# 1.net
KiCad netlist of a schematic drawn in EAGLE
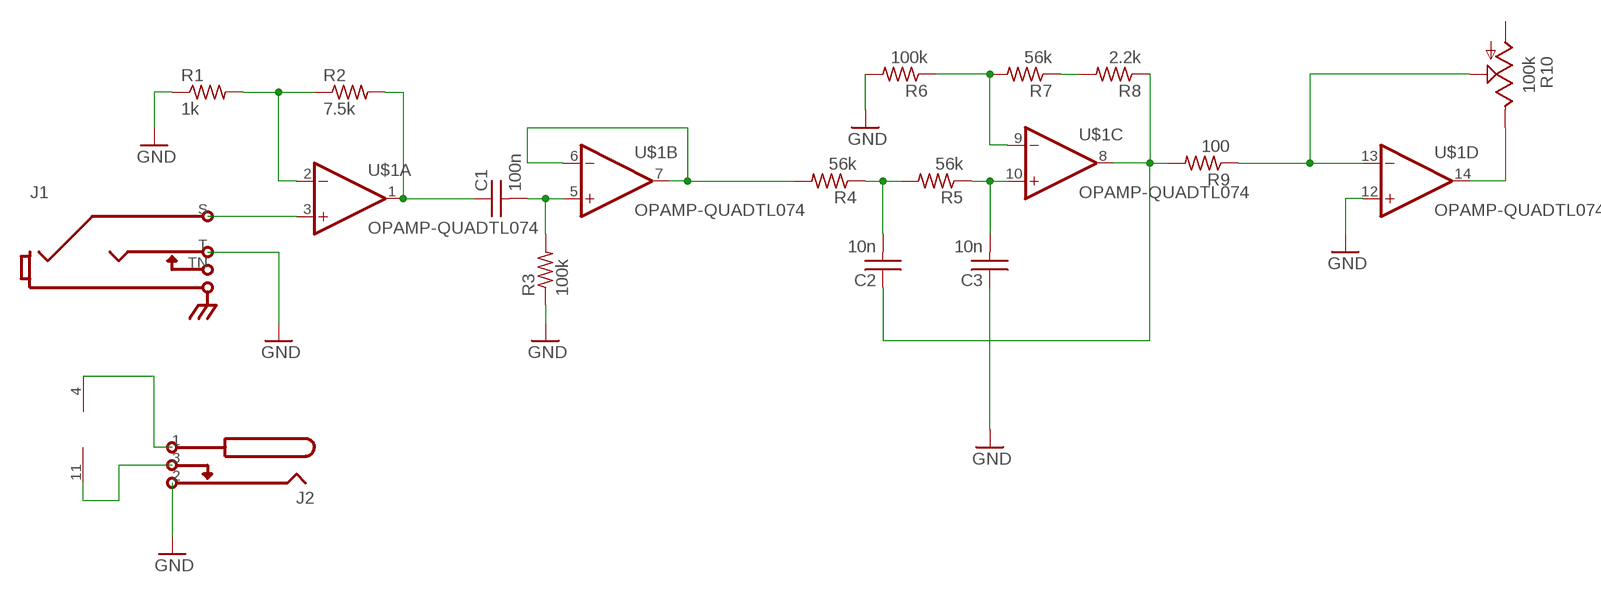
[diagram p0: schematic, sheet 1]

(export (version "E")
  (design (tool "Eeschema 10.0.6"))
  (components
    (comp (ref "C1")
      (value "100n")
      (footprint "eagle-import:BOX-2.5MM-7.2MM")
      (libsource (lib "eagle-import") (part "CAPACITOR"))
    )
    (comp (ref "C2")
      (value "10n")
      (footprint "eagle-import:BOX-2.5MM-7.2MM")
      (libsource (lib "eagle-import") (part "CAPACITOR"))
    )
    (comp (ref "C3")
      (value "10n")
      (footprint "eagle-import:BOX-2.5MM-7.2MM")
      (libsource (lib "eagle-import") (part "CAPACITOR"))
    )
    (comp (ref "J1")
      (value "MONOSW1GND")
      (footprint "eagle-import:NEUTRIK-NRJ4HM-1")
      (libsource (lib "eagle-import") (part "MONOSW1GND"))
    )
    (comp (ref "J2")
      (value "BOSS-SWITCHING")
      (footprint "eagle-import:KOBICONN-163-5010-E")
      (libsource (lib "eagle-import") (part "BOSS-SWITCHING"))
    )
    (comp (ref "R1")
      (value "1k")
      (footprint "eagle-import:0.25W-0.4IN-CARBONCOMP")
      (libsource (lib "eagle-import") (part "RESISTOR0.25W-0.4IN-CARBONCOMP"))
    )
    (comp (ref "R2")
      (value "7.5k")
      (footprint "eagle-import:0.25W-0.4IN-CARBONCOMP")
      (libsource (lib "eagle-import") (part "RESISTOR0.25W-0.4IN-CARBONCOMP"))
    )
    (comp (ref "R3")
      (value "100k")
      (footprint "eagle-import:0.25W-0.4IN-CARBONCOMP")
      (libsource (lib "eagle-import") (part "RESISTOR0.25W-0.4IN-CARBONCOMP"))
    )
    (comp (ref "R4")
      (value "56k")
      (footprint "eagle-import:0.25W-0.4IN-CARBONCOMP")
      (libsource (lib "eagle-import") (part "RESISTOR0.25W-0.4IN-CARBONCOMP"))
    )
    (comp (ref "R5")
      (value "56k")
      (footprint "eagle-import:0.25W-0.4IN-CARBONCOMP")
      (libsource (lib "eagle-import") (part "RESISTOR0.25W-0.4IN-CARBONCOMP"))
    )
    (comp (ref "R6")
      (value "100k")
      (footprint "eagle-import:0.25W-0.4IN-CARBONCOMP")
      (libsource (lib "eagle-import") (part "RESISTOR0.25W-0.4IN-CARBONCOMP"))
    )
    (comp (ref "R7")
      (value "56k")
      (footprint "eagle-import:0.25W-0.4IN-CARBONCOMP")
      (libsource (lib "eagle-import") (part "RESISTOR0.25W-0.4IN-CARBONCOMP"))
    )
    (comp (ref "R8")
      (value "2.2k")
      (footprint "eagle-import:0.25W-0.4IN-CARBONCOMP")
      (libsource (lib "eagle-import") (part "RESISTOR0.25W-0.4IN-CARBONCOMP"))
    )
    (comp (ref "R9")
      (value "100")
      (footprint "eagle-import:0.25W-0.4IN-CARBONCOMP")
      (libsource (lib "eagle-import") (part "RESISTOR0.25W-0.4IN-CARBONCOMP"))
    )
    (comp (ref "R10")
      (value "100k")
      (footprint "eagle-import:POT-SIDE-16MM-BITECH-P160KN")
      (libsource (lib "eagle-import") (part "POTENTIOMETERHORIZONTAL"))
    )
    (comp (ref "U$1")
      (value "OPAMP-QUADTL074")
      (footprint "eagle-import:DIP14")
      (libsource (lib "eagle-import") (part "OPAMP-QUADTL074"))
    )
  )
  (nets
    (net (code "1") (name "0") (class "Default")
      (node (ref "C3") (pin "P$1") (pinfunction "1_P$1") (pintype "passive"))
      (node (ref "J1") (pin "T") (pinfunction "T_T") (pintype "passive"))
      (node (ref "J2") (pin "2") (pinfunction "VCC_2") (pintype "passive"))
      (node (ref "R1") (pin "1") (pinfunction "1_1") (pintype "passive"))
      (node (ref "R3") (pin "1") (pinfunction "1_1") (pintype "passive"))
      (node (ref "R6") (pin "2") (pinfunction "2_2") (pintype "passive"))
      (node (ref "U$1") (pin "12") (pinfunction "IN+_12") (pintype "input"))
    )
    (net (code "2") (name "Net-(C1-1)") (class "Default")
      (node (ref "C1") (pin "P$1") (pinfunction "1_P$1") (pintype "passive"))
      (node (ref "R2") (pin "2") (pinfunction "2_2") (pintype "passive"))
      (node (ref "U$1") (pin "1") (pinfunction "OUT_1") (pintype "output"))
    )
    (net (code "3") (name "Net-(C1-2)") (class "Default")
      (node (ref "C1") (pin "P$2") (pinfunction "2_P$2") (pintype "passive"))
      (node (ref "R3") (pin "2") (pinfunction "2_2") (pintype "passive"))
      (node (ref "U$1") (pin "5") (pinfunction "IN+_5") (pintype "input"))
    )
    (net (code "4") (name "Net-(C2-1)") (class "Default")
      (node (ref "C2") (pin "P$1") (pinfunction "1_P$1") (pintype "passive"))
      (node (ref "R8") (pin "1") (pinfunction "1_1") (pintype "passive"))
      (node (ref "R9") (pin "2") (pinfunction "2_2") (pintype "passive"))
      (node (ref "U$1") (pin "8") (pinfunction "OUT_8") (pintype "output"))
    )
    (net (code "5") (name "Net-(C2-2)") (class "Default")
      (node (ref "C2") (pin "P$2") (pinfunction "2_P$2") (pintype "passive"))
      (node (ref "R4") (pin "1") (pinfunction "1_1") (pintype "passive"))
      (node (ref "R5") (pin "2") (pinfunction "2_2") (pintype "passive"))
    )
    (net (code "6") (name "Net-(C3-2)") (class "Default")
      (node (ref "C3") (pin "P$2") (pinfunction "2_P$2") (pintype "passive"))
      (node (ref "R5") (pin "1") (pinfunction "1_1") (pintype "passive"))
      (node (ref "U$1") (pin "10") (pinfunction "IN+_10") (pintype "input"))
    )
    (net (code "7") (name "Net-(J2-GND)") (class "Default")
      (node (ref "J2") (pin "1") (pinfunction "GND_1") (pintype "passive"))
      (node (ref "U$1") (pin "4") (pinfunction "VCC_4") (pintype "power_in"))
    )
    (net (code "8") (name "Net-(J2-SW)") (class "Default")
      (node (ref "J2") (pin "3") (pinfunction "SW_3") (pintype "passive"))
      (node (ref "U$1") (pin "11") (pinfunction "VEE_11") (pintype "power_in"))
    )
    (net (code "9") (name "Net-(R7-Pad1)") (class "Default")
      (node (ref "R7") (pin "1") (pinfunction "1_1") (pintype "passive"))
      (node (ref "R8") (pin "2") (pinfunction "2_2") (pintype "passive"))
    )
    (net (code "10") (name "Net-(R10-2)") (class "Default")
      (node (ref "R10") (pin "P$2") (pinfunction "2_P$2") (pintype "passive"))
      (node (ref "R9") (pin "1") (pinfunction "1_1") (pintype "passive"))
      (node (ref "U$1") (pin "13") (pinfunction "IN-_13") (pintype "input"))
    )
    (net (code "11") (name "Net-(R10-3)") (class "Default")
      (node (ref "R10") (pin "P$3") (pinfunction "3_P$3") (pintype "passive"))
      (node (ref "U$1") (pin "14") (pinfunction "OUT_14") (pintype "output"))
    )
    (net (code "12") (name "Net-(U$1A-IN+)") (class "Default")
      (node (ref "J1") (pin "S") (pinfunction "S_S") (pintype "passive"))
      (node (ref "U$1") (pin "3") (pinfunction "IN+_3") (pintype "input"))
    )
    (net (code "13") (name "Net-(U$1A-IN-)") (class "Default")
      (node (ref "R1") (pin "2") (pinfunction "2_2") (pintype "passive"))
      (node (ref "R2") (pin "1") (pinfunction "1_1") (pintype "passive"))
      (node (ref "U$1") (pin "2") (pinfunction "IN-_2") (pintype "input"))
    )
    (net (code "14") (name "Net-(U$1B-IN-)") (class "Default")
      (node (ref "R4") (pin "2") (pinfunction "2_2") (pintype "passive"))
      (node (ref "U$1") (pin "6") (pinfunction "IN-_6") (pintype "input"))
      (node (ref "U$1") (pin "7") (pinfunction "OUT_7") (pintype "output"))
    )
    (net (code "15") (name "Net-(U$1C-IN-)") (class "Default")
      (node (ref "R6") (pin "1") (pinfunction "1_1") (pintype "passive"))
      (node (ref "R7") (pin "2") (pinfunction "2_2") (pintype "passive"))
      (node (ref "U$1") (pin "9") (pinfunction "IN-_9") (pintype "input"))
    )
    (net (code "16") (name "unconnected-(J1-PadTN)") (class "Default")
      (node (ref "J1") (pin "TN") (pinfunction "TN_TN") (pintype "passive"))
    )
    (net (code "17") (name "unconnected-(R10-1-PadP$1)") (class "Default")
      (node (ref "R10") (pin "P$1") (pinfunction "1_P$1") (pintype "passive"))
    )
  )
)
